# LKS_EVB_MCU074D_V1_0.net
KiCad netlist of a schematic drawn in Altium Designer
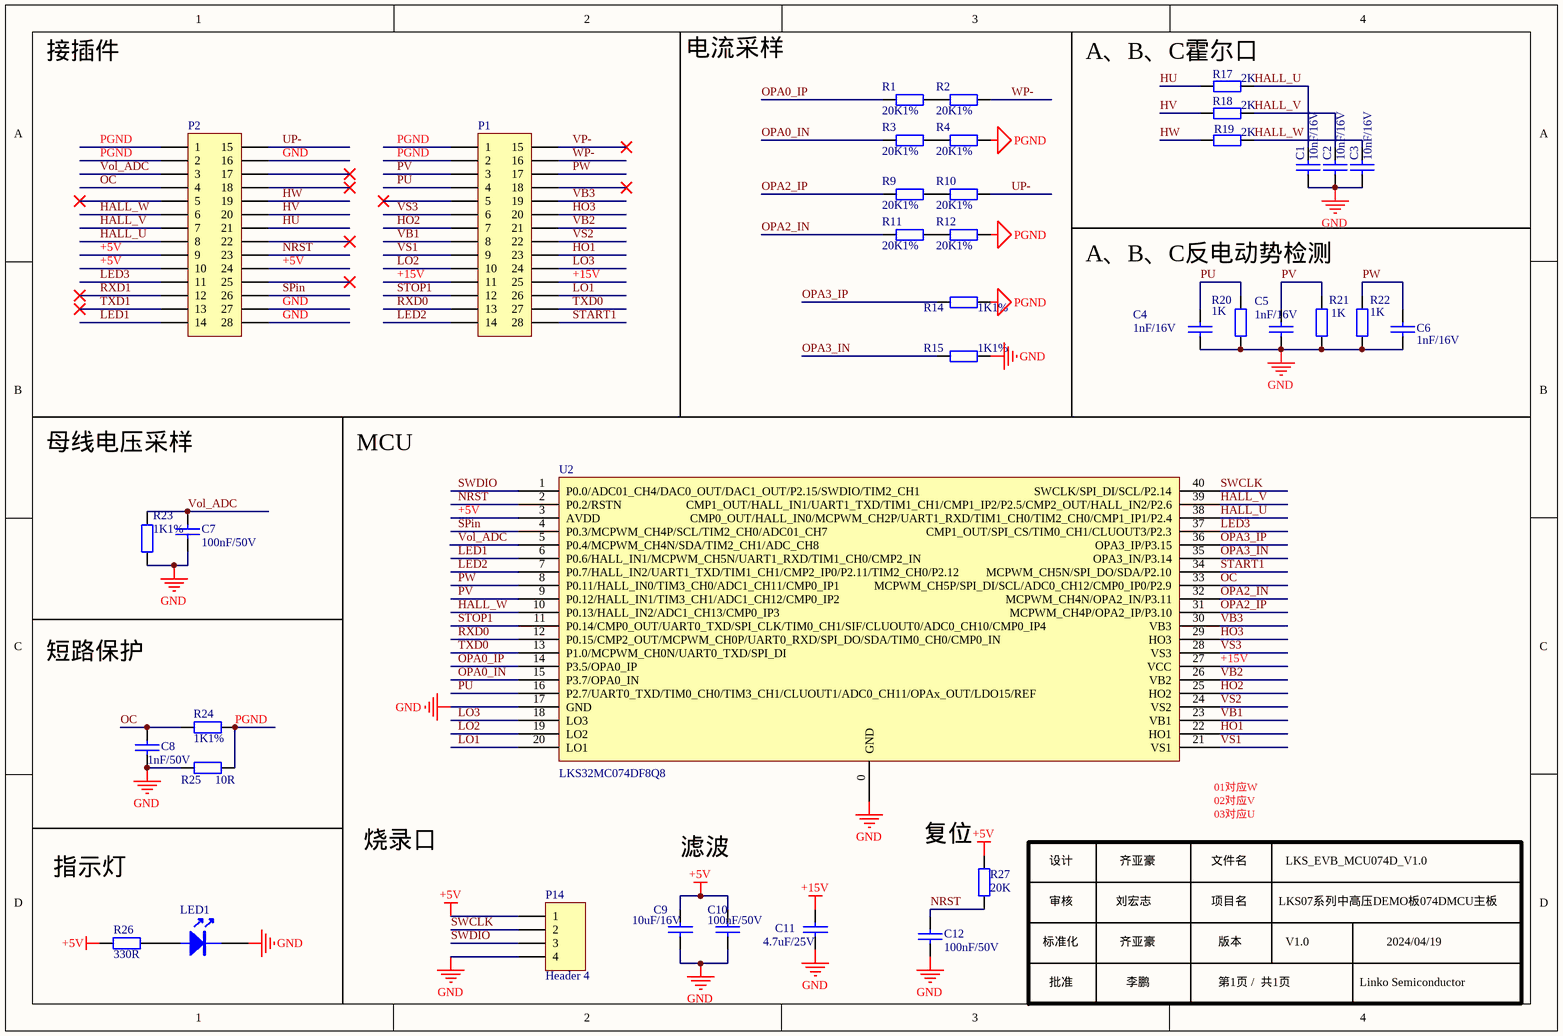
[diagram p0: LKS_EVB_MCU074D_V1.0.SchDoc]

(export (version "E")
  (design (tool "Eeschema 10.0.6"))
  (components
    (comp (ref "C1")
      (value "10nF/16V")
      (footprint "0603C")
      (description "Capacitor")
      (libsource (lib "*") (part "CAP"))
    )
    (comp (ref "C2")
      (value "10nF/16V")
      (footprint "0603C")
      (description "Capacitor")
      (libsource (lib "*") (part "CAP"))
    )
    (comp (ref "C3")
      (value "10nF/16V")
      (footprint "0603C")
      (description "Capacitor")
      (libsource (lib "*") (part "CAP"))
    )
    (comp (ref "C4")
      (value "1nF/16V")
      (footprint "0603C")
      (description "Capacitor")
      (libsource (lib "*") (part "CAP"))
    )
    (comp (ref "C5")
      (value "1nF/16V")
      (footprint "0603C")
      (description "Capacitor")
      (libsource (lib "*") (part "CAP"))
    )
    (comp (ref "C6")
      (value "1nF/16V")
      (footprint "0603C")
      (description "Capacitor")
      (libsource (lib "*") (part "CAP"))
    )
    (comp (ref "C7")
      (value "100nF/50V")
      (footprint "0603C")
      (description "Capacitor")
      (libsource (lib "*") (part "C"))
    )
    (comp (ref "C8")
      (value "1nF/50V")
      (footprint "0603C")
      (description "Capacitor")
      (libsource (lib "*") (part "C"))
    )
    (comp (ref "C9")
      (value "10uF/16V")
      (footprint "0603C")
      (description "Capacitor")
      (libsource (lib "*") (part "C"))
    )
    (comp (ref "C10")
      (value "100nF/50V")
      (footprint "0603C")
      (description "Capacitor")
      (libsource (lib "*") (part "C"))
    )
    (comp (ref "C11")
      (value "4.7uF/25V")
      (footprint "0603C")
      (description "Capacitor")
      (libsource (lib "*") (part "C"))
    )
    (comp (ref "C12")
      (value "100nF/50V")
      (footprint "0603C")
      (description "Capacitor")
      (libsource (lib "*") (part "C"))
    )
    (comp (ref "LED1")
      (value "LED")
      (footprint "LED 0603R")
      (description "LED_Light")
      (libsource (lib "LINKO_V1.0") (part "LED"))
    )
    (comp (ref "P1")
      (value "Header 14X2A")
      (footprint "HDR 2X14 底层")
      (description "Header, 14-Pin, Dual row")
      (fields (field (name "PUBLISHER") "Altium Limited"))
      (libsource (lib "Miscellaneous Connectors") (part "Header 14X2A"))
    )
    (comp (ref "P2")
      (value "Header 14X2A")
      (footprint "HDR 2X14 底层")
      (description "Header, 14-Pin, Dual row")
      (fields (field (name "PUBLISHER") "Altium Limited"))
      (libsource (lib "Miscellaneous Connectors") (part "Header 14X2A"))
    )
    (comp (ref "P14")
      (value "Header 4")
      (footprint "HDR1X4")
      (description "Header, 4-Pin")
      (fields (field (name "PUBLISHER") "Altium Limited"))
      (libsource (lib "Miscellaneous Connectors") (part "Header 4"))
    )
    (comp (ref "R1")
      (value "20K1%")
      (footprint "0603R")
      (description "Resistor")
      (fields (field (name "PUBLISHER") "Altium Limited"))
      (libsource (lib "") (part "Res_1"))
    )
    (comp (ref "R2")
      (value "20K1%")
      (footprint "0603R")
      (description "Resistor")
      (fields (field (name "PUBLISHER") "Altium Limited"))
      (libsource (lib "") (part "Res_1"))
    )
    (comp (ref "R3")
      (value "20K1%")
      (footprint "0603R")
      (description "Resistor")
      (fields (field (name "PUBLISHER") "Altium Limited"))
      (libsource (lib "") (part "Res_1"))
    )
    (comp (ref "R4")
      (value "20K1%")
      (footprint "0603R")
      (description "Resistor")
      (fields (field (name "PUBLISHER") "Altium Limited"))
      (libsource (lib "") (part "Res_1"))
    )
    (comp (ref "R9")
      (value "20K1%")
      (footprint "0603R")
      (description "Resistor")
      (fields (field (name "PUBLISHER") "Altium Limited"))
      (libsource (lib "") (part "Res_1"))
    )
    (comp (ref "R10")
      (value "20K1%")
      (footprint "0603R")
      (description "Resistor")
      (fields (field (name "PUBLISHER") "Altium Limited"))
      (libsource (lib "") (part "Res_1"))
    )
    (comp (ref "R11")
      (value "20K1%")
      (footprint "0603R")
      (description "Resistor")
      (fields (field (name "PUBLISHER") "Altium Limited"))
      (libsource (lib "") (part "Res_1"))
    )
    (comp (ref "R12")
      (value "20K1%")
      (footprint "0603R")
      (description "Resistor")
      (fields (field (name "PUBLISHER") "Altium Limited"))
      (libsource (lib "") (part "Res_1"))
    )
    (comp (ref "R14")
      (value "1K1%")
      (footprint "0603R")
      (description "Resistor")
      (fields (field (name "PUBLISHER") "Altium Limited"))
      (libsource (lib "") (part "Res_1"))
    )
    (comp (ref "R15")
      (value "1K1%")
      (footprint "0603R")
      (description "Resistor")
      (fields (field (name "PUBLISHER") "Altium Limited"))
      (libsource (lib "") (part "Res_1"))
    )
    (comp (ref "R17")
      (value "2K")
      (footprint "0603R")
      (description "Resistor")
      (fields (field (name "PUBLISHER") "Altium Limited"))
      (libsource (lib "") (part "Res_2"))
    )
    (comp (ref "R18")
      (value "2K")
      (footprint "0603R")
      (description "Resistor")
      (fields (field (name "PUBLISHER") "Altium Limited"))
      (libsource (lib "") (part "Res_2"))
    )
    (comp (ref "R19")
      (value "2K")
      (footprint "0603R")
      (description "Resistor")
      (fields (field (name "PUBLISHER") "Altium Limited"))
      (libsource (lib "") (part "Res_2"))
    )
    (comp (ref "R20")
      (value "1K")
      (footprint "0603R")
      (description "Resistor")
      (fields (field (name "PUBLISHER") "Altium Limited"))
      (libsource (lib "") (part "Res_1"))
    )
    (comp (ref "R21")
      (value "1K")
      (footprint "0603R")
      (description "Resistor")
      (fields (field (name "PUBLISHER") "Altium Limited"))
      (libsource (lib "") (part "Res_1"))
    )
    (comp (ref "R22")
      (value "1K")
      (footprint "0603R")
      (description "Resistor")
      (fields (field (name "PUBLISHER") "Altium Limited"))
      (libsource (lib "") (part "Res_1"))
    )
    (comp (ref "R23")
      (value "1K1%")
      (footprint "0603R")
      (description "Resistor")
      (fields (field (name "PUBLISHER") "Altium Limited"))
      (libsource (lib "LINKO_V1.0") (part "Res"))
    )
    (comp (ref "R24")
      (value "1K1%")
      (footprint "0603R")
      (description "Resistor")
      (fields (field (name "PUBLISHER") "Altium Limited"))
      (libsource (lib "") (part "Res_2"))
    )
    (comp (ref "R25")
      (value "10R")
      (footprint "0603R")
      (description "Resistor")
      (fields (field (name "PUBLISHER") "Altium Limited"))
      (libsource (lib "") (part "Res_1"))
    )
    (comp (ref "R26")
      (value "330R")
      (footprint "0603R")
      (description "Resistor")
      (fields (field (name "PUBLISHER") "Altium Limited"))
      (libsource (lib "") (part "Res_1"))
    )
    (comp (ref "R27")
      (value "20K")
      (footprint "0603R")
      (description "Resistor")
      (fields (field (name "PUBLISHER") "Altium Limited"))
      (libsource (lib "LINKO_V1.0") (part "Res"))
    )
    (comp (ref "U2")
      (value "LKS32MC074DF8Q8")
      (footprint "QFN40")
      (description "芯片")
      (libsource (lib "Q_LINKO_V1.0") (part "LKS32MC074DF8Q8"))
    )
  )
  (nets
    (net (code "1") (name "+5V") (class "Default")
      (node (ref "C10") (pin "2") (pinfunction "2_2") (pintype "passive"))
      (node (ref "C9") (pin "2") (pinfunction "2_2") (pintype "passive"))
      (node (ref "P14") (pin "1") (pinfunction "1_1") (pintype "passive"))
      (node (ref "P2") (pin "10") (pinfunction "10_10") (pintype "passive"))
      (node (ref "P2") (pin "24") (pinfunction "24_24") (pintype "passive"))
      (node (ref "P2") (pin "9") (pinfunction "9_9") (pintype "passive"))
      (node (ref "R26") (pin "2") (pinfunction "2_2") (pintype "passive"))
      (node (ref "R27") (pin "2") (pinfunction "2_2") (pintype "passive"))
      (node (ref "U2") (pin "3") (pinfunction "AVDD_3") (pintype "passive"))
    )
    (net (code "2") (name "+15V") (class "Default")
      (node (ref "C11") (pin "2") (pinfunction "2_2") (pintype "passive"))
      (node (ref "P1") (pin "11") (pinfunction "11_11") (pintype "passive"))
      (node (ref "P1") (pin "25") (pinfunction "25_25") (pintype "passive"))
      (node (ref "U2") (pin "27") (pinfunction "VCC_27") (pintype "passive"))
    )
    (net (code "5") (name "/HALL_U") (class "Default")
      (node (ref "C1") (pin "1") (pinfunction "1_1") (pintype "passive"))
      (node (ref "P2") (pin "8") (pinfunction "8_8") (pintype "passive"))
      (node (ref "R17") (pin "2") (pinfunction "2_2") (pintype "passive"))
      (node (ref "U2") (pin "38") (pinfunction "CMP0_OUT/HALL_IN0/MCPWM_CH2P/UART1_RXD/TIM1_CH0/TIM2_CH0/CMP1_IP1/P2.4_38") (pintype "passive"))
    )
    (net (code "6") (name "/HALL_V") (class "Default")
      (node (ref "C2") (pin "1") (pinfunction "1_1") (pintype "passive"))
      (node (ref "P2") (pin "7") (pinfunction "7_7") (pintype "passive"))
      (node (ref "R18") (pin "2") (pinfunction "2_2") (pintype "passive"))
      (node (ref "U2") (pin "39") (pinfunction "CMP1_OUT/HALL_IN1/UART1_TXD/TIM1_CH1/CMP1_IP2/P2.5/CMP2_OUT/HALL_IN2/P2.6_39") (pintype "passive"))
    )
    (net (code "7") (name "/HALL_W") (class "Default")
      (node (ref "C3") (pin "1") (pinfunction "1_1") (pintype "passive"))
      (node (ref "P2") (pin "6") (pinfunction "6_6") (pintype "passive"))
      (node (ref "R19") (pin "2") (pinfunction "2_2") (pintype "passive"))
      (node (ref "U2") (pin "10") (pinfunction "P0.13/HALL_IN2/ADC1_CH13/CMP0_IP3_10") (pintype "passive"))
    )
    (net (code "8") (name "/HO1") (class "Default")
      (node (ref "P1") (pin "23") (pinfunction "23_23") (pintype "passive"))
      (node (ref "U2") (pin "22") (pinfunction "HO1_22") (pintype "passive"))
    )
    (net (code "9") (name "/HO2") (class "Default")
      (node (ref "P1") (pin "7") (pinfunction "7_7") (pintype "passive"))
      (node (ref "U2") (pin "25") (pinfunction "HO2_25") (pintype "passive"))
    )
    (net (code "10") (name "/HO3") (class "Default")
      (node (ref "P1") (pin "20") (pinfunction "20_20") (pintype "passive"))
      (node (ref "U2") (pin "29") (pinfunction "HO3_29") (pintype "passive"))
    )
    (net (code "11") (name "/HU") (class "Default")
      (node (ref "P2") (pin "21") (pinfunction "21_21") (pintype "passive"))
      (node (ref "R17") (pin "1") (pinfunction "1_1") (pintype "passive"))
    )
    (net (code "12") (name "/HV") (class "Default")
      (node (ref "P2") (pin "20") (pinfunction "20_20") (pintype "passive"))
      (node (ref "R18") (pin "1") (pinfunction "1_1") (pintype "passive"))
    )
    (net (code "13") (name "/HW") (class "Default")
      (node (ref "P2") (pin "19") (pinfunction "19_19") (pintype "passive"))
      (node (ref "R19") (pin "1") (pinfunction "1_1") (pintype "passive"))
    )
    (net (code "14") (name "/LED1") (class "Default")
      (node (ref "P2") (pin "14") (pinfunction "14_14") (pintype "passive"))
      (node (ref "U2") (pin "6") (pinfunction "P0.6/HALL_IN1/MCPWM_CH5N/UART1_RXD/TIM1_CH0/CMP2_IN_6") (pintype "passive"))
    )
    (net (code "15") (name "/LED2") (class "Default")
      (node (ref "P1") (pin "14") (pinfunction "14_14") (pintype "passive"))
      (node (ref "U2") (pin "7") (pinfunction "P0.7/HALL_IN2/UART1_TXD/TIM1_CH1/CMP2_IP0/P2.11/TIM2_CH0/P2.12_7") (pintype "passive"))
    )
    (net (code "16") (name "/LED3") (class "Default")
      (node (ref "P2") (pin "11") (pinfunction "11_11") (pintype "passive"))
      (node (ref "U2") (pin "37") (pinfunction "CMP1_OUT/SPI_CS/TIM0_CH1/CLUOUT3/P2.3_37") (pintype "passive"))
    )
    (net (code "17") (name "/LO1") (class "Default")
      (node (ref "P1") (pin "26") (pinfunction "26_26") (pintype "passive"))
      (node (ref "U2") (pin "20") (pinfunction "LO1_20") (pintype "passive"))
    )
    (net (code "18") (name "/LO2") (class "Default")
      (node (ref "P1") (pin "10") (pinfunction "10_10") (pintype "passive"))
      (node (ref "U2") (pin "19") (pinfunction "LO2_19") (pintype "passive"))
    )
    (net (code "19") (name "/LO3") (class "Default")
      (node (ref "P1") (pin "24") (pinfunction "24_24") (pintype "passive"))
      (node (ref "U2") (pin "18") (pinfunction "LO3_18") (pintype "passive"))
    )
    (net (code "21") (name "/NRST") (class "Default")
      (node (ref "C12") (pin "1") (pinfunction "1_1") (pintype "passive"))
      (node (ref "P2") (pin "23") (pinfunction "23_23") (pintype "passive"))
      (node (ref "R27") (pin "1") (pinfunction "1_1") (pintype "passive"))
      (node (ref "U2") (pin "2") (pinfunction "P0.2/RSTN_2") (pintype "passive"))
    )
    (net (code "22") (name "/OC") (class "Default")
      (node (ref "C8") (pin "2") (pinfunction "2_2") (pintype "passive"))
      (node (ref "P2") (pin "4") (pinfunction "4_4") (pintype "passive"))
      (node (ref "R24") (pin "1") (pinfunction "1_1") (pintype "passive"))
      (node (ref "U2") (pin "33") (pinfunction "MCPWM_CH5P/SPI_DI/SCL/ADC0_CH12/CMP0_IP0/P2.9_33") (pintype "passive"))
    )
    (net (code "23") (name "/OPA0_IN") (class "Default")
      (node (ref "R3") (pin "2") (pinfunction "2_2") (pintype "passive"))
      (node (ref "U2") (pin "15") (pinfunction "P3.7/OPA0_IN_15") (pintype "passive"))
    )
    (net (code "24") (name "/OPA0_IP") (class "Default")
      (node (ref "R1") (pin "2") (pinfunction "2_2") (pintype "passive"))
      (node (ref "U2") (pin "14") (pinfunction "P3.5/OPA0_IP_14") (pintype "passive"))
    )
    (net (code "25") (name "/OPA2_IN") (class "Default")
      (node (ref "R11") (pin "2") (pinfunction "2_2") (pintype "passive"))
      (node (ref "U2") (pin "32") (pinfunction "MCPWM_CH4N/OPA2_IN/P3.11_32") (pintype "passive"))
    )
    (net (code "26") (name "/OPA2_IP") (class "Default")
      (node (ref "R9") (pin "2") (pinfunction "2_2") (pintype "passive"))
      (node (ref "U2") (pin "31") (pinfunction "MCPWM_CH4P/OPA2_IP/P3.10_31") (pintype "passive"))
    )
    (net (code "27") (name "/OPA3_IN") (class "Default")
      (node (ref "R15") (pin "2") (pinfunction "2_2") (pintype "passive"))
      (node (ref "U2") (pin "35") (pinfunction "OPA3_IN/P3.14_35") (pintype "passive"))
    )
    (net (code "28") (name "/OPA3_IP") (class "Default")
      (node (ref "R14") (pin "2") (pinfunction "2_2") (pintype "passive"))
      (node (ref "U2") (pin "36") (pinfunction "OPA3_IP/P3.15_36") (pintype "passive"))
    )
    (net (code "29") (name "/PU") (class "Default")
      (node (ref "C4") (pin "1") (pinfunction "1_1") (pintype "passive"))
      (node (ref "P1") (pin "4") (pinfunction "4_4") (pintype "passive"))
      (node (ref "R20") (pin "1") (pinfunction "1_1") (pintype "passive"))
      (node (ref "U2") (pin "16") (pinfunction "P2.7/UART0_TXD/TIM0_CH0/TIM3_CH1/CLUOUT1/ADC0_CH11/OPAx_OUT/LDO15/REF_16") (pintype "passive"))
    )
    (net (code "30") (name "/PV") (class "Default")
      (node (ref "C5") (pin "1") (pinfunction "1_1") (pintype "passive"))
      (node (ref "P1") (pin "3") (pinfunction "3_3") (pintype "passive"))
      (node (ref "R21") (pin "1") (pinfunction "1_1") (pintype "passive"))
      (node (ref "U2") (pin "9") (pinfunction "P0.12/HALL_IN1/TIM3_CH1/ADC1_CH12/CMP0_IP2_9") (pintype "passive"))
    )
    (net (code "31") (name "/PW") (class "Default")
      (node (ref "C6") (pin "1") (pinfunction "1_1") (pintype "passive"))
      (node (ref "P1") (pin "17") (pinfunction "17_17") (pintype "passive"))
      (node (ref "R22") (pin "1") (pinfunction "1_1") (pintype "passive"))
      (node (ref "U2") (pin "8") (pinfunction "P0.11/HALL_IN0/TIM3_CH0/ADC1_CH11/CMP0_IP1_8") (pintype "passive"))
    )
    (net (code "32") (name "/RXD0") (class "Default")
      (node (ref "P1") (pin "13") (pinfunction "13_13") (pintype "passive"))
      (node (ref "U2") (pin "12") (pinfunction "P0.15/CMP2_OUT/MCPWM_CH0P/UART0_RXD/SPI_DO/SDA/TIM0_CH0/CMP0_IN_12") (pintype "passive"))
    )
    (net (code "33") (name "/RXD1") (class "Default")
      (node (ref "P2") (pin "12") (pinfunction "12_12") (pintype "passive+no_connect"))
    )
    (net (code "34") (name "/SPin") (class "Default")
      (node (ref "P2") (pin "26") (pinfunction "26_26") (pintype "passive"))
      (node (ref "U2") (pin "4") (pinfunction "P0.3/MCPWM_CH4P/SCL/TIM2_CH0/ADC01_CH7_4") (pintype "passive"))
    )
    (net (code "35") (name "/START1") (class "Default")
      (node (ref "P1") (pin "28") (pinfunction "28_28") (pintype "passive"))
      (node (ref "U2") (pin "34") (pinfunction "MCPWM_CH5N/SPI_DO/SDA/P2.10_34") (pintype "passive"))
    )
    (net (code "36") (name "/STOP1") (class "Default")
      (node (ref "P1") (pin "12") (pinfunction "12_12") (pintype "passive"))
      (node (ref "U2") (pin "11") (pinfunction "P0.14/CMP0_OUT/UART0_TXD/SPI_CLK/TIM0_CH1/SIF/CLUOUT0/ADC0_CH10/CMP0_IP4_11") (pintype "passive"))
    )
    (net (code "37") (name "/SWCLK") (class "Default")
      (node (ref "P14") (pin "2") (pinfunction "2_2") (pintype "passive"))
      (node (ref "U2") (pin "40") (pinfunction "SWCLK/SPI_DI/SCL/P2.14_40") (pintype "passive"))
    )
    (net (code "38") (name "/SWDIO") (class "Default")
      (node (ref "P14") (pin "3") (pinfunction "3_3") (pintype "passive"))
      (node (ref "U2") (pin "1") (pinfunction "P0.0/ADC01_CH4/DAC0_OUT/DAC1_OUT/P2.15/SWDIO/TIM2_CH1_1") (pintype "passive"))
    )
    (net (code "39") (name "/TXD0") (class "Default")
      (node (ref "P1") (pin "27") (pinfunction "27_27") (pintype "passive"))
      (node (ref "U2") (pin "13") (pinfunction "P1.0/MCPWM_CH0N/UART0_TXD/SPI_DI_13") (pintype "passive"))
    )
    (net (code "40") (name "/TXD1") (class "Default")
      (node (ref "P2") (pin "13") (pinfunction "13_13") (pintype "passive+no_connect"))
    )
    (net (code "41") (name "/UP-") (class "Default")
      (node (ref "P2") (pin "15") (pinfunction "15_15") (pintype "passive"))
      (node (ref "R10") (pin "1") (pinfunction "1_1") (pintype "passive"))
    )
    (net (code "42") (name "/VB1") (class "Default")
      (node (ref "P1") (pin "8") (pinfunction "8_8") (pintype "passive"))
      (node (ref "U2") (pin "23") (pinfunction "VB1_23") (pintype "passive"))
    )
    (net (code "43") (name "/VB2") (class "Default")
      (node (ref "P1") (pin "21") (pinfunction "21_21") (pintype "passive"))
      (node (ref "U2") (pin "26") (pinfunction "VB2_26") (pintype "passive"))
    )
    (net (code "44") (name "/VB3") (class "Default")
      (node (ref "P1") (pin "19") (pinfunction "19_19") (pintype "passive"))
      (node (ref "U2") (pin "30") (pinfunction "VB3_30") (pintype "passive"))
    )
    (net (code "45") (name "/VP-") (class "Default")
      (node (ref "P1") (pin "15") (pinfunction "15_15") (pintype "passive+no_connect"))
    )
    (net (code "46") (name "/VS1") (class "Default")
      (node (ref "P1") (pin "9") (pinfunction "9_9") (pintype "passive"))
      (node (ref "U2") (pin "21") (pinfunction "VS1_21") (pintype "passive"))
    )
    (net (code "47") (name "/VS2") (class "Default")
      (node (ref "P1") (pin "22") (pinfunction "22_22") (pintype "passive"))
      (node (ref "U2") (pin "24") (pinfunction "VS2_24") (pintype "passive"))
    )
    (net (code "48") (name "/VS3") (class "Default")
      (node (ref "P1") (pin "6") (pinfunction "6_6") (pintype "passive"))
      (node (ref "U2") (pin "28") (pinfunction "VS3_28") (pintype "passive"))
    )
    (net (code "49") (name "/Vol_ADC") (class "Default")
      (node (ref "C7") (pin "2") (pinfunction "2_2") (pintype "passive"))
      (node (ref "P2") (pin "3") (pinfunction "3_3") (pintype "passive"))
      (node (ref "R23") (pin "2") (pinfunction "2_2") (pintype "passive"))
      (node (ref "U2") (pin "5") (pinfunction "P0.4/MCPWM_CH4N/SDA/TIM2_CH1/ADC_CH8_5") (pintype "passive"))
    )
    (net (code "50") (name "/WP-") (class "Default")
      (node (ref "P1") (pin "16") (pinfunction "16_16") (pintype "passive"))
      (node (ref "R2") (pin "1") (pinfunction "1_1") (pintype "passive"))
    )
    (net (code "52") (name "GND") (class "Default")
      (node (ref "C1") (pin "2") (pinfunction "2_2") (pintype "passive"))
      (node (ref "C10") (pin "1") (pinfunction "1_1") (pintype "passive"))
      (node (ref "C11") (pin "1") (pinfunction "1_1") (pintype "passive"))
      (node (ref "C12") (pin "2") (pinfunction "2_2") (pintype "passive"))
      (node (ref "C2") (pin "2") (pinfunction "2_2") (pintype "passive"))
      (node (ref "C3") (pin "2") (pinfunction "2_2") (pintype "passive"))
      (node (ref "C4") (pin "2") (pinfunction "2_2") (pintype "passive"))
      (node (ref "C5") (pin "2") (pinfunction "2_2") (pintype "passive"))
      (node (ref "C6") (pin "2") (pinfunction "2_2") (pintype "passive"))
      (node (ref "C7") (pin "1") (pinfunction "1_1") (pintype "passive"))
      (node (ref "C8") (pin "1") (pinfunction "1_1") (pintype "passive"))
      (node (ref "C9") (pin "1") (pinfunction "1_1") (pintype "passive"))
      (node (ref "LED1") (pin "2") (pinfunction "K_2") (pintype "passive"))
      (node (ref "P14") (pin "4") (pinfunction "4_4") (pintype "passive"))
      (node (ref "P2") (pin "16") (pinfunction "16_16") (pintype "passive"))
      (node (ref "P2") (pin "27") (pinfunction "27_27") (pintype "passive"))
      (node (ref "P2") (pin "28") (pinfunction "28_28") (pintype "passive"))
      (node (ref "R15") (pin "1") (pinfunction "1_1") (pintype "passive"))
      (node (ref "R20") (pin "2") (pinfunction "2_2") (pintype "passive"))
      (node (ref "R21") (pin "2") (pinfunction "2_2") (pintype "passive"))
      (node (ref "R22") (pin "2") (pinfunction "2_2") (pintype "passive"))
      (node (ref "R23") (pin "1") (pinfunction "1_1") (pintype "passive"))
      (node (ref "R25") (pin "2") (pinfunction "2_2") (pintype "passive"))
      (node (ref "U2") (pin "0") (pinfunction "GND_0") (pintype "passive"))
      (node (ref "U2") (pin "17") (pinfunction "GND_17") (pintype "passive"))
    )
    (net (code "53") (name "Net-(LED1-A)") (class "Default")
      (node (ref "LED1") (pin "1") (pinfunction "A_1") (pintype "passive"))
      (node (ref "R26") (pin "1") (pinfunction "1_1") (pintype "passive"))
    )
    (net (code "54") (name "Net-(R1-Pad1)") (class "Default")
      (node (ref "R1") (pin "1") (pinfunction "1_1") (pintype "passive"))
      (node (ref "R2") (pin "2") (pinfunction "2_2") (pintype "passive"))
    )
    (net (code "55") (name "Net-(R3-Pad1)") (class "Default")
      (node (ref "R3") (pin "1") (pinfunction "1_1") (pintype "passive"))
      (node (ref "R4") (pin "2") (pinfunction "2_2") (pintype "passive"))
    )
    (net (code "56") (name "Net-(R10-Pad2)") (class "Default")
      (node (ref "R10") (pin "2") (pinfunction "2_2") (pintype "passive"))
      (node (ref "R9") (pin "1") (pinfunction "1_1") (pintype "passive"))
    )
    (net (code "57") (name "Net-(R11-Pad1)") (class "Default")
      (node (ref "R11") (pin "1") (pinfunction "1_1") (pintype "passive"))
      (node (ref "R12") (pin "2") (pinfunction "2_2") (pintype "passive"))
    )
    (net (code "58") (name "PGND") (class "Default")
      (node (ref "P1") (pin "1") (pinfunction "1_1") (pintype "passive"))
      (node (ref "P1") (pin "2") (pinfunction "2_2") (pintype "passive"))
      (node (ref "P2") (pin "1") (pinfunction "1_1") (pintype "passive"))
      (node (ref "P2") (pin "2") (pinfunction "2_2") (pintype "passive"))
      (node (ref "R12") (pin "1") (pinfunction "1_1") (pintype "passive"))
      (node (ref "R14") (pin "1") (pinfunction "1_1") (pintype "passive"))
      (node (ref "R24") (pin "2") (pinfunction "2_2") (pintype "passive"))
      (node (ref "R25") (pin "1") (pinfunction "1_1") (pintype "passive"))
      (node (ref "R4") (pin "1") (pinfunction "1_1") (pintype "passive"))
    )
    (net (code "59") (name "unconnected-(P1-Pad5)") (class "Default")
      (node (ref "P1") (pin "5") (pinfunction "5_5") (pintype "passive+no_connect"))
    )
    (net (code "60") (name "unconnected-(P1-Pad18)") (class "Default")
      (node (ref "P1") (pin "18") (pinfunction "18_18") (pintype "passive+no_connect"))
    )
    (net (code "61") (name "unconnected-(P2-Pad5)") (class "Default")
      (node (ref "P2") (pin "5") (pinfunction "5_5") (pintype "passive+no_connect"))
    )
    (net (code "62") (name "unconnected-(P2-Pad17)") (class "Default")
      (node (ref "P2") (pin "17") (pinfunction "17_17") (pintype "passive+no_connect"))
    )
    (net (code "63") (name "unconnected-(P2-Pad18)") (class "Default")
      (node (ref "P2") (pin "18") (pinfunction "18_18") (pintype "passive+no_connect"))
    )
    (net (code "64") (name "unconnected-(P2-Pad22)") (class "Default")
      (node (ref "P2") (pin "22") (pinfunction "22_22") (pintype "passive+no_connect"))
    )
    (net (code "65") (name "unconnected-(P2-Pad25)") (class "Default")
      (node (ref "P2") (pin "25") (pinfunction "25_25") (pintype "passive+no_connect"))
    )
  )
)
